# Relays.net
KiCad netlist of a schematic drawn in Altium Designer
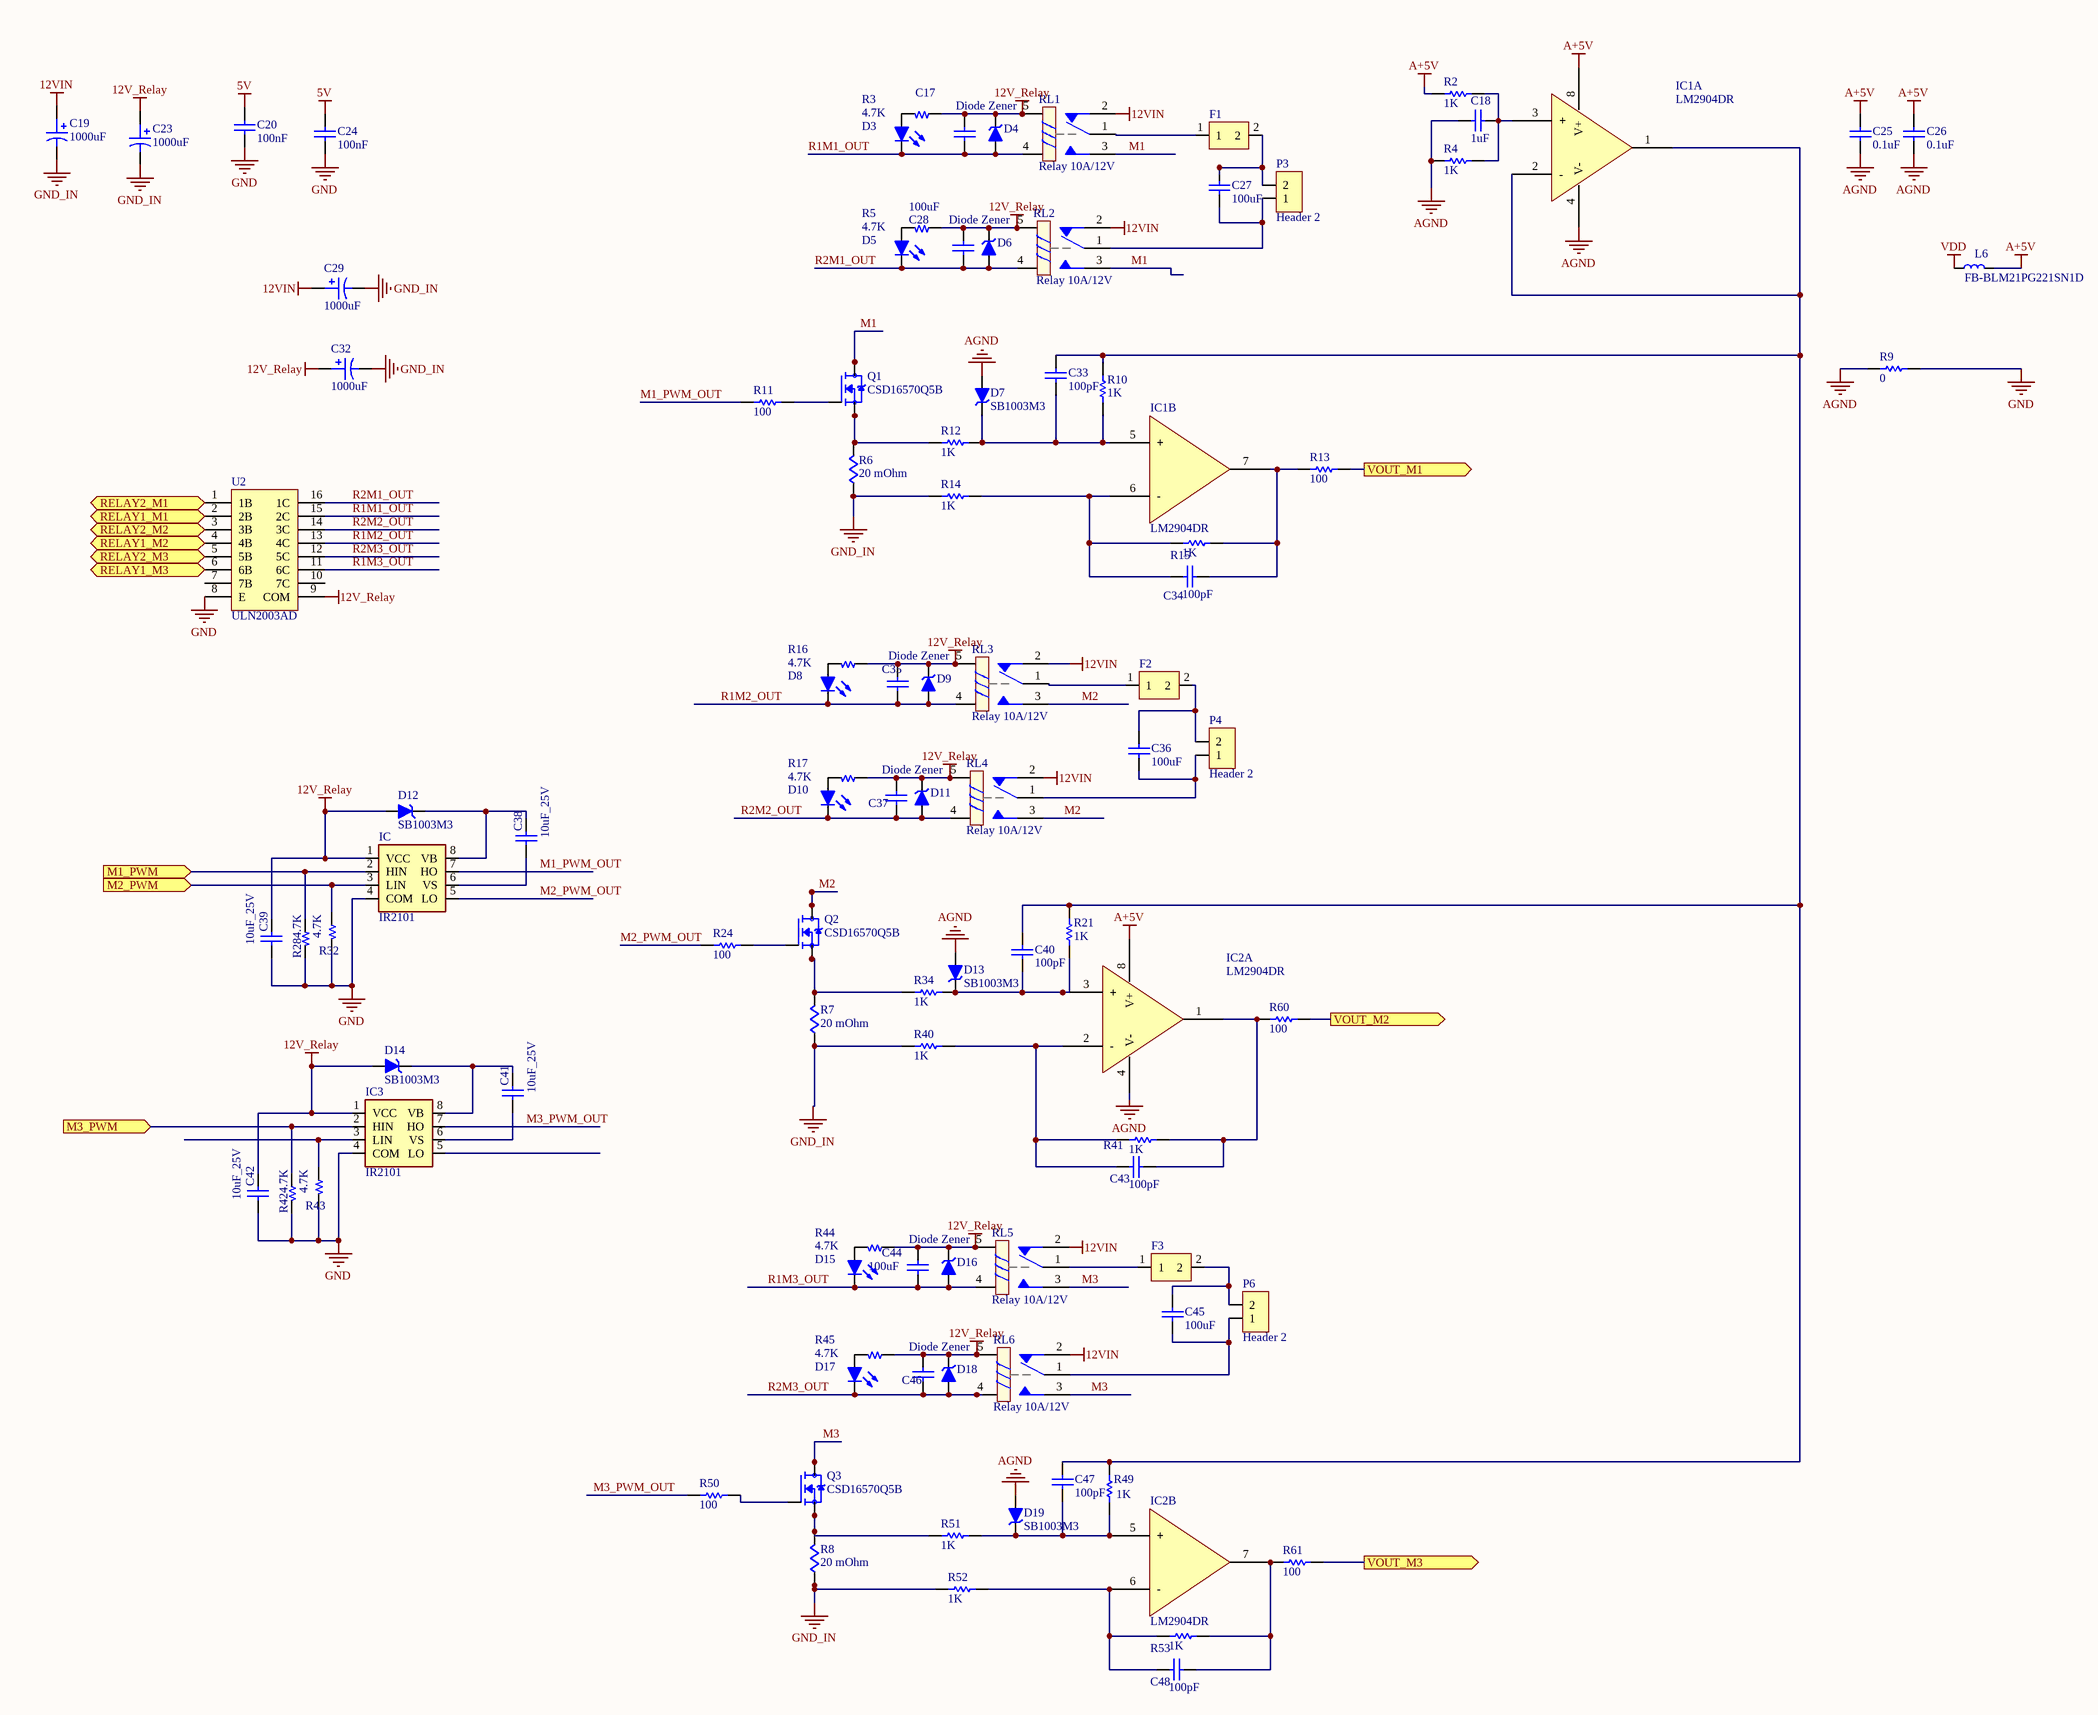
[diagram p0: Relays.SchDoc]

(export (version "E")
  (design (tool "Eeschema 10.0.6"))
  (components
    (comp (ref "C17")
      (value "Cap Non-pol")
      (footprint "C 0805")
      (description "Non-polarized Capacitor")
      (fields (field (name "PUBLISHER") "Altium Limited"))
      (libsource (lib "phong") (part "Cap Non-pol"))
    )
    (comp (ref "C18")
      (value "1uF")
      (footprint "C 0805")
      (description "Non-polarized Capacitor")
      (fields (field (name "Comment") "Cap Non-pol") (field (name "PUBLISHER") "Altium Limited"))
      (libsource (lib "phong") (part "Cap Non-pol"))
    )
    (comp (ref "C19")
      (value "1000uF")
      (footprint "CAP/D100/H200/LS50")
      (description "Polarized Capacitor")
      (fields (field (name "Comment") "Cap Pol") (field (name "PUBLISHER") "Altium Limited"))
      (libsource (lib "phong") (part "Cap Pol"))
    )
    (comp (ref "C20")
      (value "100nF")
      (footprint "C 0805")
      (description "Non-polarized Capacitor")
      (fields (field (name "Comment") "Cap Non-pol") (field (name "PUBLISHER") "Altium Limited"))
      (libsource (lib "phong") (part "Cap Non-pol"))
    )
    (comp (ref "C23")
      (value "1000uF")
      (footprint "CAP/D100/H200/LS50")
      (description "Polarized Capacitor")
      (fields (field (name "Comment") "Cap Pol") (field (name "PUBLISHER") "Altium Limited"))
      (libsource (lib "phong") (part "Cap Pol"))
    )
    (comp (ref "C24")
      (value "100nF")
      (footprint "C 0805")
      (description "Non-polarized Capacitor")
      (fields (field (name "Comment") "Cap Non-pol") (field (name "PUBLISHER") "Altium Limited"))
      (libsource (lib "phong") (part "Cap Non-pol"))
    )
    (comp (ref "C25")
      (value "0.1uF")
      (footprint "C 0805")
      (description "Non-polarized Capacitor")
      (fields (field (name "Comment") "Cap Non-pol") (field (name "PUBLISHER") "Altium Limited"))
      (libsource (lib "phong") (part "Cap Non-pol"))
    )
    (comp (ref "C26")
      (value "0.1uF")
      (footprint "C 0805")
      (description "Non-polarized Capacitor")
      (fields (field (name "Comment") "Cap Non-pol") (field (name "PUBLISHER") "Altium Limited"))
      (libsource (lib "phong") (part "Cap Non-pol"))
    )
    (comp (ref "C27")
      (value "100uF")
      (footprint "CAP Ceramic/W200")
      (description "Non-polarized Capacitor")
      (fields (field (name "Comment") "Cap Non-pol") (field (name "PUBLISHER") "Altium Limited"))
      (libsource (lib "phong") (part "Cap Non-pol"))
    )
    (comp (ref "C28")
      (value "100uF")
      (footprint "C 0805")
      (description "Non-polarized Capacitor")
      (fields (field (name "Comment") "Cap Non-pol") (field (name "PUBLISHER") "Altium Limited"))
      (libsource (lib "phong") (part "Cap Non-pol"))
    )
    (comp (ref "C29")
      (value "1000uF")
      (footprint "CAP/D100/H200/LS50")
      (description "Polarized Capacitor")
      (fields (field (name "Comment") "Cap Pol") (field (name "PUBLISHER") "Altium Limited"))
      (libsource (lib "phong") (part "Cap Pol"))
    )
    (comp (ref "C32")
      (value "1000uF")
      (footprint "CAP/D100/H200/LS50")
      (description "Polarized Capacitor")
      (fields (field (name "Comment") "Cap Pol") (field (name "PUBLISHER") "Altium Limited"))
      (libsource (lib "phong") (part "Cap Pol"))
    )
    (comp (ref "C33")
      (value "100pF")
      (footprint "C 0805")
      (description "Non-polarized Capacitor")
      (fields (field (name "Comment") "Cap Non-pol") (field (name "PUBLISHER") "Altium Limited"))
      (libsource (lib "phong") (part "Cap Non-pol"))
    )
    (comp (ref "C34")
      (value "100pF")
      (footprint "C 0805")
      (description "Non-polarized Capacitor")
      (fields (field (name "Comment") "Cap Non-pol") (field (name "PUBLISHER") "Altium Limited"))
      (libsource (lib "phong") (part "Cap Non-pol"))
    )
    (comp (ref "C35")
      (value "Cap Non-pol")
      (footprint "C 0805")
      (description "Non-polarized Capacitor")
      (fields (field (name "PUBLISHER") "Altium Limited"))
      (libsource (lib "phong") (part "Cap Non-pol"))
    )
    (comp (ref "C36")
      (value "100uF")
      (footprint "CAP Ceramic/W200")
      (description "Non-polarized Capacitor")
      (fields (field (name "Comment") "Cap Non-pol") (field (name "PUBLISHER") "Altium Limited"))
      (libsource (lib "phong") (part "Cap Non-pol"))
    )
    (comp (ref "C37")
      (value "Cap Non-pol")
      (footprint "C 0805")
      (description "Non-polarized Capacitor")
      (fields (field (name "PUBLISHER") "Altium Limited"))
      (libsource (lib "phong") (part "Cap Non-pol"))
    )
    (comp (ref "C38")
      (value "10uF_25V")
      (footprint "C 0805")
      (description "Non-polarized Capacitor")
      (fields (field (name "PUBLISHER") "Altium Limited"))
      (libsource (lib "phong") (part "Cap Non-pol"))
    )
    (comp (ref "C39")
      (value "10uF_25V")
      (footprint "C 0805")
      (description "Non-polarized Capacitor")
      (fields (field (name "PUBLISHER") "Altium Limited"))
      (libsource (lib "phong") (part "Cap Non-pol"))
    )
    (comp (ref "C40")
      (value "100pF")
      (footprint "C 0805")
      (description "Non-polarized Capacitor")
      (fields (field (name "Comment") "Cap Non-pol") (field (name "PUBLISHER") "Altium Limited"))
      (libsource (lib "phong") (part "Cap Non-pol"))
    )
    (comp (ref "C41")
      (value "10uF_25V")
      (footprint "C 0805")
      (description "Non-polarized Capacitor")
      (fields (field (name "PUBLISHER") "Altium Limited"))
      (libsource (lib "phong") (part "Cap Non-pol"))
    )
    (comp (ref "C42")
      (value "10uF_25V")
      (footprint "C 0805")
      (description "Non-polarized Capacitor")
      (fields (field (name "PUBLISHER") "Altium Limited"))
      (libsource (lib "phong") (part "Cap Non-pol"))
    )
    (comp (ref "C43")
      (value "100pF")
      (footprint "C 0805")
      (description "Non-polarized Capacitor")
      (fields (field (name "Comment") "Cap Non-pol") (field (name "PUBLISHER") "Altium Limited"))
      (libsource (lib "phong") (part "Cap Non-pol"))
    )
    (comp (ref "C44")
      (value "100uF")
      (footprint "C 0805")
      (description "Non-polarized Capacitor")
      (fields (field (name "Comment") "Cap Non-pol") (field (name "PUBLISHER") "Altium Limited"))
      (libsource (lib "phong") (part "Cap Non-pol"))
    )
    (comp (ref "C45")
      (value "100uF")
      (footprint "CAP Ceramic/W200")
      (description "Non-polarized Capacitor")
      (fields (field (name "Comment") "Cap Non-pol") (field (name "PUBLISHER") "Altium Limited"))
      (libsource (lib "phong") (part "Cap Non-pol"))
    )
    (comp (ref "C46")
      (value "Cap Non-pol")
      (footprint "C 0805")
      (description "Non-polarized Capacitor")
      (fields (field (name "PUBLISHER") "Altium Limited"))
      (libsource (lib "phong") (part "Cap Non-pol"))
    )
    (comp (ref "C47")
      (value "100pF")
      (footprint "C 0805")
      (description "Non-polarized Capacitor")
      (fields (field (name "Comment") "Cap Non-pol") (field (name "PUBLISHER") "Altium Limited"))
      (libsource (lib "phong") (part "Cap Non-pol"))
    )
    (comp (ref "C48")
      (value "100pF")
      (footprint "C 0805")
      (description "Non-polarized Capacitor")
      (fields (field (name "Comment") "Cap Non-pol") (field (name "PUBLISHER") "Altium Limited"))
      (libsource (lib "phong") (part "Cap Non-pol"))
    )
    (comp (ref "D3")
      (value "Led")
      (footprint "Led 0805 RED")
      (description "LED RED CLEAR 0805 SMD")
      (libsource (lib "chipfc_altium_libs") (part "Led"))
    )
    (comp (ref "D4")
      (value "Diode Zener")
      (footprint "SOD80C Wave")
      (description "Zener Diode")
      (fields (field (name "PUBLISHER") "Altium Limited"))
      (libsource (lib "BKIT4U_LIB") (part "Diode Zener"))
    )
    (comp (ref "D5")
      (value "Led")
      (footprint "Led 0805 RED")
      (description "LED RED CLEAR 0805 SMD")
      (libsource (lib "chipfc_altium_libs") (part "Led"))
    )
    (comp (ref "D6")
      (value "Diode Zener")
      (footprint "SOD80C Wave")
      (description "Zener Diode")
      (fields (field (name "PUBLISHER") "Altium Limited"))
      (libsource (lib "BKIT4U_LIB") (part "Diode Zener"))
    )
    (comp (ref "D7")
      (value "SB1003M3")
      (footprint "DO-214AC (SMA)")
      (description "Zener Diode")
      (libsource (lib "ChipFC_Lib") (part "Diode Zener"))
    )
    (comp (ref "D8")
      (value "Led")
      (footprint "Led 0805 RED")
      (description "LED RED CLEAR 0805 SMD")
      (libsource (lib "chipfc_altium_libs") (part "Led"))
    )
    (comp (ref "D9")
      (value "Diode Zener")
      (footprint "SOD80C Wave")
      (description "Zener Diode")
      (fields (field (name "PUBLISHER") "Altium Limited"))
      (libsource (lib "BKIT4U_LIB") (part "Diode Zener"))
    )
    (comp (ref "D10")
      (value "Led")
      (footprint "Led 0805 RED")
      (description "LED RED CLEAR 0805 SMD")
      (libsource (lib "chipfc_altium_libs") (part "Led"))
    )
    (comp (ref "D11")
      (value "Diode Zener")
      (footprint "SOD80C Wave")
      (description "Zener Diode")
      (fields (field (name "PUBLISHER") "Altium Limited"))
      (libsource (lib "BKIT4U_LIB") (part "Diode Zener"))
    )
    (comp (ref "D12")
      (value "SB1003M3")
      (footprint "DO-214AC (SMA)")
      (description "Zener Diode")
      (libsource (lib "ChipFC_Lib") (part "Diode Zener"))
    )
    (comp (ref "D13")
      (value "SB1003M3")
      (footprint "DO-214AC (SMA)")
      (description "Zener Diode")
      (libsource (lib "ChipFC_Lib") (part "Diode Zener"))
    )
    (comp (ref "D14")
      (value "SB1003M3")
      (footprint "DO-214AC (SMA)")
      (description "Zener Diode")
      (libsource (lib "ChipFC_Lib") (part "Diode Zener"))
    )
    (comp (ref "D15")
      (value "Led")
      (footprint "Led 0805 RED")
      (description "LED RED CLEAR 0805 SMD")
      (libsource (lib "chipfc_altium_libs") (part "Led"))
    )
    (comp (ref "D16")
      (value "Diode Zener")
      (footprint "SOD80C Wave")
      (description "Zener Diode")
      (fields (field (name "PUBLISHER") "Altium Limited"))
      (libsource (lib "BKIT4U_LIB") (part "Diode Zener"))
    )
    (comp (ref "D17")
      (value "Led")
      (footprint "Led 0805 RED")
      (description "LED RED CLEAR 0805 SMD")
      (libsource (lib "chipfc_altium_libs") (part "Led"))
    )
    (comp (ref "D18")
      (value "Diode Zener")
      (footprint "SOD80C Wave")
      (description "Zener Diode")
      (fields (field (name "PUBLISHER") "Altium Limited"))
      (libsource (lib "BKIT4U_LIB") (part "Diode Zener"))
    )
    (comp (ref "D19")
      (value "SB1003M3")
      (footprint "DO-214AC (SMA)")
      (description "Zener Diode")
      (libsource (lib "ChipFC_Lib") (part "Diode Zener"))
    )
    (comp (ref "F1")
      (value "FUSE_DCAR_HOLDER")
      (footprint "DCAR Fuse holder")
      (libsource (lib "FUSE_DCAR_HOLDER") (part "FUSE_DCAR_HOLDER"))
    )
    (comp (ref "F2")
      (value "FUSE_DCAR_HOLDER")
      (footprint "DCAR Fuse holder")
      (libsource (lib "FUSE_DCAR_HOLDER") (part "FUSE_DCAR_HOLDER"))
    )
    (comp (ref "F3")
      (value "FUSE_DCAR_HOLDER")
      (footprint "DCAR Fuse holder")
      (libsource (lib "FUSE_DCAR_HOLDER") (part "FUSE_DCAR_HOLDER"))
    )
    (comp (ref "IC")
      (value "IR2101")
      (footprint "SOIC-8-I/SN")
      (description "Half-Bridge Gate Driver IC Non-Inverting 8-SOIC")
      (fields (field (name "MF") "Infineon"))
      (libsource (lib "IR2101") (part "IR2101"))
    )
    (comp (ref "IC1")
      (value "LM2904DR")
      (footprint "SOIC-8-I/SN")
      (description "IC OPAMP GP 2 CIRCUIT 8SOIC")
      (fields (field (name "MANUFACTURER") "Texas Instruments"))
      (libsource (lib "Celestial Altium Library - altium_library") (part "TI LM2904DR"))
    )
    (comp (ref "IC2")
      (value "LM2904DR")
      (footprint "SOIC-8-I/SN")
      (description "IC OPAMP GP 2 CIRCUIT 8SOIC")
      (fields (field (name "MANUFACTURER") "Texas Instruments"))
      (libsource (lib "Celestial Altium Library - altium_library") (part "TI LM2904DR"))
    )
    (comp (ref "IC3")
      (value "IR2101")
      (footprint "SOIC-8-I/SN")
      (description "Half-Bridge Gate Driver IC Non-Inverting 8-SOIC")
      (fields (field (name "MF") "Infineon"))
      (libsource (lib "IR2101") (part "IR2101"))
    )
    (comp (ref "L6")
      (value "FB-BLM21PG221SN1D")
      (footprint "L 0805 (2012)")
      (description "Inductor")
      (libsource (lib "chipfc_altium_libs") (part "Inductor"))
    )
    (comp (ref "P3")
      (value "Header 2")
      (footprint "HDR Domino 2")
      (description "Header, 2-Pin")
      (fields (field (name "PUBLISHER") "Altium Limited"))
      (libsource (lib "BKIT4U_LIB") (part "Header 2"))
    )
    (comp (ref "P4")
      (value "Header 2")
      (footprint "HDR Domino 2")
      (description "Header, 2-Pin")
      (fields (field (name "PUBLISHER") "Altium Limited"))
      (libsource (lib "BKIT4U_LIB") (part "Header 2"))
    )
    (comp (ref "P6")
      (value "Header 2")
      (footprint "HDR Domino 2")
      (description "Header, 2-Pin")
      (fields (field (name "PUBLISHER") "Altium Limited"))
      (libsource (lib "BKIT4U_LIB") (part "Header 2"))
    )
    (comp (ref "Q1")
      (value "CSD16570Q5B")
      (footprint "TRANS_CSD19502Q5BT")
      (description "N-Channel 30V 35A _Ta_ 2.8W _Ta_, 53W _Tc_ Surface Mount 8-VSONP _3x3.15_")
      (fields (field (name "MP") "CSD17577Q3A") (field (name "MF") "Texas Instruments"))
      (libsource (lib "CSD17577Q3A") (part "CSD17577Q3A"))
    )
    (comp (ref "Q2")
      (value "CSD16570Q5B")
      (footprint "TRANS_CSD19502Q5BT")
      (description "N-Channel 30V 35A _Ta_ 2.8W _Ta_, 53W _Tc_ Surface Mount 8-VSONP _3x3.15_")
      (fields (field (name "MP") "CSD17577Q3A") (field (name "MF") "Texas Instruments"))
      (libsource (lib "CSD17577Q3A") (part "CSD17577Q3A"))
    )
    (comp (ref "Q3")
      (value "CSD16570Q5B")
      (footprint "TRANS_CSD19502Q5BT")
      (description "N-Channel 30V 35A _Ta_ 2.8W _Ta_, 53W _Tc_ Surface Mount 8-VSONP _3x3.15_")
      (fields (field (name "MP") "CSD17577Q3A") (field (name "MF") "Texas Instruments"))
      (libsource (lib "CSD17577Q3A") (part "CSD17577Q3A"))
    )
    (comp (ref "R2")
      (value "1K")
      (footprint "R 0805")
      (description "Resistor")
      (fields (field (name "PUBLISHER") "Altium Limited"))
      (libsource (lib "BKIT4U_LIB") (part "Resistor"))
    )
    (comp (ref "R3")
      (value "4.7K")
      (footprint "R 0805")
      (description "RES SMD 4.7K OHM 1% 1/10W 0805")
      (libsource (lib "chipfc_altium_libs") (part "Resistor"))
    )
    (comp (ref "R4")
      (value "1K")
      (footprint "R 0805")
      (description "Resistor")
      (fields (field (name "PUBLISHER") "Altium Limited"))
      (libsource (lib "BKIT4U_LIB") (part "Resistor"))
    )
    (comp (ref "R5")
      (value "4.7K")
      (footprint "R 0805")
      (description "RES SMD 4.7K OHM 1% 1/10W 0805")
      (libsource (lib "chipfc_altium_libs") (part "Resistor"))
    )
    (comp (ref "R6")
      (value "20 mOhm")
      (footprint "R2512")
      (fields (field (name "Comment") "Resistor2"))
      (libsource (lib "AltiumOpenLibs") (part "Resistor2"))
    )
    (comp (ref "R7")
      (value "20 mOhm")
      (footprint "R2512")
      (fields (field (name "Comment") "Resistor2"))
      (libsource (lib "AltiumOpenLibs") (part "Resistor2"))
    )
    (comp (ref "R8")
      (value "20 mOhm")
      (footprint "R2512")
      (fields (field (name "Comment") "Resistor2"))
      (libsource (lib "AltiumOpenLibs") (part "Resistor2"))
    )
    (comp (ref "R9")
      (value "0")
      (footprint "R 0805")
      (description "Resistor")
      (fields (field (name "PUBLISHER") "Altium Limited"))
      (libsource (lib "BKIT4U_LIB") (part "Resistor"))
    )
    (comp (ref "R10")
      (value "1K")
      (footprint "R 0805")
      (description "Resistor")
      (fields (field (name "PUBLISHER") "Altium Limited"))
      (libsource (lib "BKIT4U_LIB") (part "Resistor"))
    )
    (comp (ref "R11")
      (value "100")
      (footprint "R 0805")
      (description "Resistor")
      (fields (field (name "PUBLISHER") "Altium Limited"))
      (libsource (lib "BKIT4U_LIB") (part "Resistor"))
    )
    (comp (ref "R12")
      (value "1K")
      (footprint "R 0805")
      (description "Resistor")
      (fields (field (name "PUBLISHER") "Altium Limited"))
      (libsource (lib "BKIT4U_LIB") (part "Resistor"))
    )
    (comp (ref "R13")
      (value "100")
      (footprint "R 0805")
      (description "Resistor")
      (fields (field (name "PUBLISHER") "Altium Limited"))
      (libsource (lib "BKIT4U_LIB") (part "Resistor"))
    )
    (comp (ref "R14")
      (value "1K")
      (footprint "R 0805")
      (description "Resistor")
      (fields (field (name "PUBLISHER") "Altium Limited"))
      (libsource (lib "BKIT4U_LIB") (part "Resistor"))
    )
    (comp (ref "R15")
      (value "1K")
      (footprint "R 0805")
      (description "Resistor")
      (fields (field (name "PUBLISHER") "Altium Limited"))
      (libsource (lib "BKIT4U_LIB") (part "Resistor"))
    )
    (comp (ref "R16")
      (value "4.7K")
      (footprint "R 0805")
      (description "RES SMD 4.7K OHM 1% 1/10W 0805")
      (libsource (lib "chipfc_altium_libs") (part "Resistor"))
    )
    (comp (ref "R17")
      (value "4.7K")
      (footprint "R 0805")
      (description "RES SMD 4.7K OHM 1% 1/10W 0805")
      (libsource (lib "chipfc_altium_libs") (part "Resistor"))
    )
    (comp (ref "R21")
      (value "1K")
      (footprint "R 0805")
      (description "Resistor")
      (fields (field (name "PUBLISHER") "Altium Limited"))
      (libsource (lib "BKIT4U_LIB") (part "Resistor"))
    )
    (comp (ref "R24")
      (value "100")
      (footprint "R 0805")
      (description "Resistor")
      (fields (field (name "PUBLISHER") "Altium Limited"))
      (libsource (lib "BKIT4U_LIB") (part "Resistor"))
    )
    (comp (ref "R28")
      (value "4.7K")
      (footprint "R 0805")
      (description "RES SMD 4.7K OHM 1% 1/10W 0805")
      (libsource (lib "chipfc_altium_libs") (part "Resistor"))
    )
    (comp (ref "R32")
      (value "4.7K")
      (footprint "R 0805")
      (description "RES SMD 4.7K OHM 1% 1/10W 0805")
      (libsource (lib "chipfc_altium_libs") (part "Resistor"))
    )
    (comp (ref "R34")
      (value "1K")
      (footprint "R 0805")
      (description "Resistor")
      (fields (field (name "PUBLISHER") "Altium Limited"))
      (libsource (lib "BKIT4U_LIB") (part "Resistor"))
    )
    (comp (ref "R40")
      (value "1K")
      (footprint "R 0805")
      (description "Resistor")
      (fields (field (name "PUBLISHER") "Altium Limited"))
      (libsource (lib "BKIT4U_LIB") (part "Resistor"))
    )
    (comp (ref "R41")
      (value "1K")
      (footprint "R 0805")
      (description "Resistor")
      (fields (field (name "PUBLISHER") "Altium Limited"))
      (libsource (lib "BKIT4U_LIB") (part "Resistor"))
    )
    (comp (ref "R42")
      (value "4.7K")
      (footprint "R 0805")
      (description "RES SMD 4.7K OHM 1% 1/10W 0805")
      (libsource (lib "chipfc_altium_libs") (part "Resistor"))
    )
    (comp (ref "R43")
      (value "4.7K")
      (footprint "R 0805")
      (description "RES SMD 4.7K OHM 1% 1/10W 0805")
      (libsource (lib "chipfc_altium_libs") (part "Resistor"))
    )
    (comp (ref "R44")
      (value "4.7K")
      (footprint "R 0805")
      (description "RES SMD 4.7K OHM 1% 1/10W 0805")
      (libsource (lib "chipfc_altium_libs") (part "Resistor"))
    )
    (comp (ref "R45")
      (value "4.7K")
      (footprint "R 0805")
      (description "RES SMD 4.7K OHM 1% 1/10W 0805")
      (libsource (lib "chipfc_altium_libs") (part "Resistor"))
    )
    (comp (ref "R49")
      (value "1K")
      (footprint "R 0805")
      (description "Resistor")
      (fields (field (name "PUBLISHER") "Altium Limited"))
      (libsource (lib "BKIT4U_LIB") (part "Resistor"))
    )
    (comp (ref "R50")
      (value "100")
      (footprint "R 0805")
      (description "Resistor")
      (fields (field (name "PUBLISHER") "Altium Limited"))
      (libsource (lib "BKIT4U_LIB") (part "Resistor"))
    )
    (comp (ref "R51")
      (value "1K")
      (footprint "R 0805")
      (description "Resistor")
      (fields (field (name "PUBLISHER") "Altium Limited"))
      (libsource (lib "BKIT4U_LIB") (part "Resistor"))
    )
    (comp (ref "R52")
      (value "1K")
      (footprint "R 0805")
      (description "Resistor")
      (fields (field (name "PUBLISHER") "Altium Limited"))
      (libsource (lib "BKIT4U_LIB") (part "Resistor"))
    )
    (comp (ref "R53")
      (value "1K")
      (footprint "R 0805")
      (description "Resistor")
      (fields (field (name "PUBLISHER") "Altium Limited"))
      (libsource (lib "BKIT4U_LIB") (part "Resistor"))
    )
    (comp (ref "R60")
      (value "100")
      (footprint "R 0805")
      (description "Resistor")
      (fields (field (name "PUBLISHER") "Altium Limited"))
      (libsource (lib "BKIT4U_LIB") (part "Resistor"))
    )
    (comp (ref "R61")
      (value "100")
      (footprint "R 0805")
      (description "Resistor")
      (fields (field (name "PUBLISHER") "Altium Limited"))
      (libsource (lib "BKIT4U_LIB") (part "Resistor"))
    )
    (comp (ref "RL1")
      (value "Relay 10A/12V")
      (footprint "RL_SPDT_20A_SMALL")
      (description "Relay SPDT,10A - 12VDC 5 Pin")
      (libsource (lib "BKIT4U_LIB") (part "Relay 1"))
    )
    (comp (ref "RL2")
      (value "Relay 10A/12V")
      (footprint "RL_SPDT_20A_SMALL")
      (description "Relay SPDT,10A - 12VDC 5 Pin")
      (libsource (lib "BKIT4U_LIB") (part "Relay 1"))
    )
    (comp (ref "RL3")
      (value "Relay 10A/12V")
      (footprint "RL_SPDT_20A_SMALL")
      (description "Relay SPDT,10A - 12VDC 5 Pin")
      (libsource (lib "BKIT4U_LIB") (part "Relay 1"))
    )
    (comp (ref "RL4")
      (value "Relay 10A/12V")
      (footprint "RL_SPDT_20A_SMALL")
      (description "Relay SPDT,10A - 12VDC 5 Pin")
      (libsource (lib "BKIT4U_LIB") (part "Relay 1"))
    )
    (comp (ref "RL5")
      (value "Relay 10A/12V")
      (footprint "RL_SPDT_20A_SMALL")
      (description "Relay SPDT,10A - 12VDC 5 Pin")
      (libsource (lib "BKIT4U_LIB") (part "Relay 1"))
    )
    (comp (ref "RL6")
      (value "Relay 10A/12V")
      (footprint "RL_SPDT_20A_SMALL")
      (description "Relay SPDT,10A - 12VDC 5 Pin")
      (libsource (lib "BKIT4U_LIB") (part "Relay 1"))
    )
    (comp (ref "U2")
      (value "ULN2003AD")
      (footprint "SOIC-16")
      (description "IC PWR RELAY 7NPN 1:1 16SOIC")
      (libsource (lib "chipfc_altium_libs") (part "ULN2003"))
    )
  )
  (nets
    (net (code "1") (name "/M1") (class "Default")
      (node (ref "Q1") (pin "9") (pinfunction "D_9") (pintype "passive"))
      (node (ref "Q1") (pin "9_1") (pinfunction "D_9_1") (pintype "passive"))
      (node (ref "Q1") (pin "9_2") (pinfunction "D_9_2") (pintype "passive"))
      (node (ref "Q1") (pin "9_3") (pinfunction "D_9_3") (pintype "passive"))
      (node (ref "Q1") (pin "9_4") (pinfunction "D_9_4") (pintype "passive"))
      (node (ref "Q1") (pin "9_5") (pinfunction "D_9_5") (pintype "passive"))
      (node (ref "Q1") (pin "9_6") (pinfunction "D_9_6") (pintype "passive"))
      (node (ref "Q1") (pin "9_7") (pinfunction "D_9_7") (pintype "passive"))
      (node (ref "RL1") (pin "3") (pinfunction "3_3") (pintype "passive"))
      (node (ref "RL2") (pin "3") (pinfunction "3_3") (pintype "passive"))
    )
    (net (code "2") (name "/M1_PWM") (class "Default")
      (node (ref "IC") (pin "2") (pinfunction "HIN_2") (pintype "bidirectional"))
      (node (ref "R28") (pin "1") (pinfunction "1_1") (pintype "passive"))
    )
    (net (code "3") (name "/M1_PWM_OUT") (class "Default")
      (node (ref "IC") (pin "7") (pinfunction "HO_7") (pintype "bidirectional"))
      (node (ref "R11") (pin "2") (pinfunction "2_2") (pintype "passive"))
    )
    (net (code "4") (name "/M2") (class "Default")
      (node (ref "Q2") (pin "9") (pinfunction "D_9") (pintype "passive"))
      (node (ref "Q2") (pin "9_1") (pinfunction "D_9_1") (pintype "passive"))
      (node (ref "Q2") (pin "9_2") (pinfunction "D_9_2") (pintype "passive"))
      (node (ref "Q2") (pin "9_3") (pinfunction "D_9_3") (pintype "passive"))
      (node (ref "Q2") (pin "9_4") (pinfunction "D_9_4") (pintype "passive"))
      (node (ref "Q2") (pin "9_5") (pinfunction "D_9_5") (pintype "passive"))
      (node (ref "Q2") (pin "9_6") (pinfunction "D_9_6") (pintype "passive"))
      (node (ref "Q2") (pin "9_7") (pinfunction "D_9_7") (pintype "passive"))
      (node (ref "RL3") (pin "3") (pinfunction "3_3") (pintype "passive"))
      (node (ref "RL4") (pin "3") (pinfunction "3_3") (pintype "passive"))
    )
    (net (code "5") (name "/M2_PWM") (class "Default")
      (node (ref "IC") (pin "3") (pinfunction "LIN_3") (pintype "bidirectional"))
      (node (ref "R32") (pin "1") (pinfunction "1_1") (pintype "passive"))
    )
    (net (code "6") (name "/M2_PWM_OUT") (class "Default")
      (node (ref "IC") (pin "5") (pinfunction "LO_5") (pintype "bidirectional"))
      (node (ref "R24") (pin "2") (pinfunction "2_2") (pintype "passive"))
    )
    (net (code "7") (name "/M3") (class "Default")
      (node (ref "Q3") (pin "9") (pinfunction "D_9") (pintype "passive"))
      (node (ref "Q3") (pin "9_1") (pinfunction "D_9_1") (pintype "passive"))
      (node (ref "Q3") (pin "9_2") (pinfunction "D_9_2") (pintype "passive"))
      (node (ref "Q3") (pin "9_3") (pinfunction "D_9_3") (pintype "passive"))
      (node (ref "Q3") (pin "9_4") (pinfunction "D_9_4") (pintype "passive"))
      (node (ref "Q3") (pin "9_5") (pinfunction "D_9_5") (pintype "passive"))
      (node (ref "Q3") (pin "9_6") (pinfunction "D_9_6") (pintype "passive"))
      (node (ref "Q3") (pin "9_7") (pinfunction "D_9_7") (pintype "passive"))
      (node (ref "RL5") (pin "3") (pinfunction "3_3") (pintype "passive"))
      (node (ref "RL6") (pin "3") (pinfunction "3_3") (pintype "passive"))
    )
    (net (code "8") (name "/M3_PWM") (class "Default")
      (node (ref "IC3") (pin "2") (pinfunction "HIN_2") (pintype "bidirectional"))
      (node (ref "R42") (pin "1") (pinfunction "1_1") (pintype "passive"))
    )
    (net (code "9") (name "/M3_PWM_OUT") (class "Default")
      (node (ref "IC3") (pin "7") (pinfunction "HO_7") (pintype "bidirectional"))
      (node (ref "R50") (pin "2") (pinfunction "2_2") (pintype "passive"))
    )
    (net (code "10") (name "/R1M1_OUT") (class "Default")
      (node (ref "C17") (pin "1") (pinfunction "1_1") (pintype "passive"))
      (node (ref "D3") (pin "2") (pinfunction "K_2") (pintype "passive"))
      (node (ref "D4") (pin "1") (pinfunction "A_1") (pintype "passive"))
      (node (ref "RL1") (pin "4") (pinfunction "4_4") (pintype "passive"))
      (node (ref "U2") (pin "15") (pinfunction "2C_15") (pintype "passive"))
    )
    (net (code "11") (name "/R1M2_OUT") (class "Default")
      (node (ref "C35") (pin "1") (pinfunction "1_1") (pintype "passive"))
      (node (ref "D8") (pin "2") (pinfunction "K_2") (pintype "passive"))
      (node (ref "D9") (pin "1") (pinfunction "A_1") (pintype "passive"))
      (node (ref "RL3") (pin "4") (pinfunction "4_4") (pintype "passive"))
      (node (ref "U2") (pin "13") (pinfunction "4C_13") (pintype "passive"))
    )
    (net (code "12") (name "/R1M3_OUT") (class "Default")
      (node (ref "C44") (pin "1") (pinfunction "1_1") (pintype "passive"))
      (node (ref "D15") (pin "2") (pinfunction "K_2") (pintype "passive"))
      (node (ref "D16") (pin "1") (pinfunction "A_1") (pintype "passive"))
      (node (ref "RL5") (pin "4") (pinfunction "4_4") (pintype "passive"))
      (node (ref "U2") (pin "11") (pinfunction "6C_11") (pintype "passive"))
    )
    (net (code "13") (name "/R2M1_OUT") (class "Default")
      (node (ref "C28") (pin "1") (pinfunction "1_1") (pintype "passive"))
      (node (ref "D5") (pin "2") (pinfunction "K_2") (pintype "passive"))
      (node (ref "D6") (pin "1") (pinfunction "A_1") (pintype "passive"))
      (node (ref "RL2") (pin "4") (pinfunction "4_4") (pintype "passive"))
      (node (ref "U2") (pin "16") (pinfunction "1C_16") (pintype "passive"))
    )
    (net (code "14") (name "/R2M2_OUT") (class "Default")
      (node (ref "C37") (pin "1") (pinfunction "1_1") (pintype "passive"))
      (node (ref "D10") (pin "2") (pinfunction "K_2") (pintype "passive"))
      (node (ref "D11") (pin "1") (pinfunction "A_1") (pintype "passive"))
      (node (ref "RL4") (pin "4") (pinfunction "4_4") (pintype "passive"))
      (node (ref "U2") (pin "14") (pinfunction "3C_14") (pintype "passive"))
    )
    (net (code "15") (name "/R2M3_OUT") (class "Default")
      (node (ref "C46") (pin "1") (pinfunction "1_1") (pintype "passive"))
      (node (ref "D17") (pin "2") (pinfunction "K_2") (pintype "passive"))
      (node (ref "D18") (pin "1") (pinfunction "A_1") (pintype "passive"))
      (node (ref "RL6") (pin "4") (pinfunction "4_4") (pintype "passive"))
      (node (ref "U2") (pin "12") (pinfunction "5C_12") (pintype "passive"))
    )
    (net (code "16") (name "/RELAY1_M1") (class "Default")
      (node (ref "U2") (pin "2") (pinfunction "2B_2") (pintype "passive"))
    )
    (net (code "17") (name "/RELAY1_M2") (class "Default")
      (node (ref "U2") (pin "4") (pinfunction "4B_4") (pintype "passive"))
    )
    (net (code "18") (name "/RELAY1_M3") (class "Default")
      (node (ref "U2") (pin "6") (pinfunction "6B_6") (pintype "passive"))
    )
    (net (code "19") (name "/RELAY2_M1") (class "Default")
      (node (ref "U2") (pin "1") (pinfunction "1B_1") (pintype "passive"))
    )
    (net (code "20") (name "/RELAY2_M2") (class "Default")
      (node (ref "U2") (pin "3") (pinfunction "3B_3") (pintype "passive"))
    )
    (net (code "21") (name "/RELAY2_M3") (class "Default")
      (node (ref "U2") (pin "5") (pinfunction "5B_5") (pintype "passive"))
    )
    (net (code "22") (name "/VOUT_M1") (class "Default")
      (node (ref "R13") (pin "1") (pinfunction "1_1") (pintype "passive"))
    )
    (net (code "23") (name "/VOUT_M2") (class "Default")
      (node (ref "R60") (pin "1") (pinfunction "1_1") (pintype "passive"))
    )
    (net (code "24") (name "/VOUT_M3") (class "Default")
      (node (ref "R61") (pin "1") (pinfunction "1_1") (pintype "passive"))
    )
    (net (code "25") (name "5V") (class "Default")
      (node (ref "C20") (pin "2") (pinfunction "2_2") (pintype "passive"))
      (node (ref "C24") (pin "2") (pinfunction "2_2") (pintype "passive"))
    )
    (net (code "26") (name "12VIN") (class "Default")
      (node (ref "C19") (pin "1") (pinfunction "1_1") (pintype "passive"))
      (node (ref "C29") (pin "1") (pinfunction "1_1") (pintype "passive"))
      (node (ref "RL1") (pin "2") (pinfunction "2_2") (pintype "passive"))
      (node (ref "RL2") (pin "2") (pinfunction "2_2") (pintype "passive"))
      (node (ref "RL3") (pin "2") (pinfunction "2_2") (pintype "passive"))
      (node (ref "RL4") (pin "2") (pinfunction "2_2") (pintype "passive"))
      (node (ref "RL5") (pin "2") (pinfunction "2_2") (pintype "passive"))
      (node (ref "RL6") (pin "2") (pinfunction "2_2") (pintype "passive"))
    )
    (net (code "27") (name "12V_Relay") (class "Default")
      (node (ref "C17") (pin "2") (pinfunction "2_2") (pintype "passive"))
      (node (ref "C23") (pin "1") (pinfunction "1_1") (pintype "passive"))
      (node (ref "C28") (pin "2") (pinfunction "2_2") (pintype "passive"))
      (node (ref "C32") (pin "1") (pinfunction "1_1") (pintype "passive"))
      (node (ref "C35") (pin "2") (pinfunction "2_2") (pintype "passive"))
      (node (ref "C37") (pin "2") (pinfunction "2_2") (pintype "passive"))
      (node (ref "C39") (pin "2") (pinfunction "2_2") (pintype "passive"))
      (node (ref "C42") (pin "2") (pinfunction "2_2") (pintype "passive"))
      (node (ref "C44") (pin "2") (pinfunction "2_2") (pintype "passive"))
      (node (ref "C46") (pin "2") (pinfunction "2_2") (pintype "passive"))
      (node (ref "D11") (pin "2") (pinfunction "K_2") (pintype "passive"))
      (node (ref "D12") (pin "1") (pinfunction "A_1") (pintype "passive"))
      (node (ref "D14") (pin "1") (pinfunction "A_1") (pintype "passive"))
      (node (ref "D16") (pin "2") (pinfunction "K_2") (pintype "passive"))
      (node (ref "D18") (pin "2") (pinfunction "K_2") (pintype "passive"))
      (node (ref "D4") (pin "2") (pinfunction "K_2") (pintype "passive"))
      (node (ref "D6") (pin "2") (pinfunction "K_2") (pintype "passive"))
      (node (ref "D9") (pin "2") (pinfunction "K_2") (pintype "passive"))
      (node (ref "IC") (pin "1") (pinfunction "VCC_1") (pintype "bidirectional"))
      (node (ref "IC3") (pin "1") (pinfunction "VCC_1") (pintype "bidirectional"))
      (node (ref "R16") (pin "1") (pinfunction "1_1") (pintype "passive"))
      (node (ref "R17") (pin "1") (pinfunction "1_1") (pintype "passive"))
      (node (ref "R3") (pin "1") (pinfunction "1_1") (pintype "passive"))
      (node (ref "R44") (pin "1") (pinfunction "1_1") (pintype "passive"))
      (node (ref "R45") (pin "1") (pinfunction "1_1") (pintype "passive"))
      (node (ref "R5") (pin "1") (pinfunction "1_1") (pintype "passive"))
      (node (ref "RL1") (pin "5") (pinfunction "5_5") (pintype "passive"))
      (node (ref "RL2") (pin "5") (pinfunction "5_5") (pintype "passive"))
      (node (ref "RL3") (pin "5") (pinfunction "5_5") (pintype "passive"))
      (node (ref "RL4") (pin "5") (pinfunction "5_5") (pintype "passive"))
      (node (ref "RL5") (pin "5") (pinfunction "5_5") (pintype "passive"))
      (node (ref "RL6") (pin "5") (pinfunction "5_5") (pintype "passive"))
      (node (ref "U2") (pin "9") (pinfunction "COM_9") (pintype "passive"))
    )
    (net (code "28") (name "A+5V") (class "Default")
      (node (ref "C25") (pin "2") (pinfunction "2_2") (pintype "passive"))
      (node (ref "C26") (pin "2") (pinfunction "2_2") (pintype "passive"))
      (node (ref "IC1") (pin "8") (pinfunction "V+_8") (pintype "passive"))
      (node (ref "IC2") (pin "8") (pinfunction "V+_8") (pintype "passive"))
      (node (ref "L6") (pin "2") (pinfunction "2_2") (pintype "passive"))
      (node (ref "R2") (pin "1") (pinfunction "1_1") (pintype "passive"))
    )
    (net (code "29") (name "AGND") (class "Default")
      (node (ref "C18") (pin "2") (pinfunction "2_2") (pintype "passive"))
      (node (ref "C25") (pin "1") (pinfunction "1_1") (pintype "passive"))
      (node (ref "C26") (pin "1") (pinfunction "1_1") (pintype "passive"))
      (node (ref "D13") (pin "1") (pinfunction "A_1") (pintype "passive"))
      (node (ref "D19") (pin "1") (pinfunction "A_1") (pintype "passive"))
      (node (ref "D7") (pin "1") (pinfunction "A_1") (pintype "passive"))
      (node (ref "IC1") (pin "4") (pinfunction "V-_4") (pintype "passive"))
      (node (ref "IC2") (pin "4") (pinfunction "V-_4") (pintype "passive"))
      (node (ref "R4") (pin "1") (pinfunction "1_1") (pintype "passive"))
      (node (ref "R9") (pin "1") (pinfunction "1_1") (pintype "passive"))
    )
    (net (code "30") (name "GND") (class "Default")
      (node (ref "C20") (pin "1") (pinfunction "1_1") (pintype "passive"))
      (node (ref "C24") (pin "1") (pinfunction "1_1") (pintype "passive"))
      (node (ref "C39") (pin "1") (pinfunction "1_1") (pintype "passive"))
      (node (ref "C42") (pin "1") (pinfunction "1_1") (pintype "passive"))
      (node (ref "IC") (pin "4") (pinfunction "COM_4") (pintype "bidirectional"))
      (node (ref "IC3") (pin "4") (pinfunction "COM_4") (pintype "bidirectional"))
      (node (ref "R28") (pin "2") (pinfunction "2_2") (pintype "passive"))
      (node (ref "R32") (pin "2") (pinfunction "2_2") (pintype "passive"))
      (node (ref "R42") (pin "2") (pinfunction "2_2") (pintype "passive"))
      (node (ref "R43") (pin "2") (pinfunction "2_2") (pintype "passive"))
      (node (ref "R9") (pin "2") (pinfunction "2_2") (pintype "passive"))
      (node (ref "U2") (pin "8") (pinfunction "E_8") (pintype "passive"))
    )
    (net (code "31") (name "GND_IN") (class "Default")
      (node (ref "C19") (pin "2") (pinfunction "2_2") (pintype "passive"))
      (node (ref "C23") (pin "2") (pinfunction "2_2") (pintype "passive"))
      (node (ref "C29") (pin "2") (pinfunction "2_2") (pintype "passive"))
      (node (ref "C32") (pin "2") (pinfunction "2_2") (pintype "passive"))
      (node (ref "R14") (pin "2") (pinfunction "2_2") (pintype "passive"))
      (node (ref "R40") (pin "2") (pinfunction "2_2") (pintype "passive"))
      (node (ref "R52") (pin "2") (pinfunction "2_2") (pintype "passive"))
      (node (ref "R6") (pin "1") (pinfunction "1_1") (pintype "passive"))
      (node (ref "R7") (pin "1") (pinfunction "1_1") (pintype "passive"))
      (node (ref "R8") (pin "1") (pinfunction "1_1") (pintype "passive"))
    )
    (net (code "32") (name "Net-(C27-Pad1)") (class "Default")
      (node (ref "C27") (pin "1") (pinfunction "1_1") (pintype "passive"))
      (node (ref "P3") (pin "1") (pinfunction "1_1") (pintype "passive"))
      (node (ref "RL2") (pin "1") (pinfunction "1_1") (pintype "passive"))
    )
    (net (code "33") (name "Net-(C27-Pad2)") (class "Default")
      (node (ref "C27") (pin "2") (pinfunction "2_2") (pintype "passive"))
      (node (ref "F1") (pin "2") (pinfunction "2_2") (pintype "passive"))
      (node (ref "P3") (pin "2") (pinfunction "2_2") (pintype "passive"))
    )
    (net (code "34") (name "Net-(C36-Pad1)") (class "Default")
      (node (ref "C36") (pin "1") (pinfunction "1_1") (pintype "passive"))
      (node (ref "P4") (pin "1") (pinfunction "1_1") (pintype "passive"))
      (node (ref "RL4") (pin "1") (pinfunction "1_1") (pintype "passive"))
    )
    (net (code "35") (name "Net-(C36-Pad2)") (class "Default")
      (node (ref "C36") (pin "2") (pinfunction "2_2") (pintype "passive"))
      (node (ref "F2") (pin "2") (pinfunction "2_2") (pintype "passive"))
      (node (ref "P4") (pin "2") (pinfunction "2_2") (pintype "passive"))
    )
    (net (code "36") (name "Net-(C45-Pad1)") (class "Default")
      (node (ref "C45") (pin "1") (pinfunction "1_1") (pintype "passive"))
      (node (ref "P6") (pin "1") (pinfunction "1_1") (pintype "passive"))
      (node (ref "RL6") (pin "1") (pinfunction "1_1") (pintype "passive"))
    )
    (net (code "37") (name "Net-(C45-Pad2)") (class "Default")
      (node (ref "C45") (pin "2") (pinfunction "2_2") (pintype "passive"))
      (node (ref "F3") (pin "2") (pinfunction "2_2") (pintype "passive"))
      (node (ref "P6") (pin "2") (pinfunction "2_2") (pintype "passive"))
    )
    (net (code "38") (name "Net-(D3-A)") (class "Default")
      (node (ref "D3") (pin "1") (pinfunction "A_1") (pintype "passive"))
      (node (ref "R3") (pin "2") (pinfunction "2_2") (pintype "passive"))
    )
    (net (code "39") (name "Net-(D5-A)") (class "Default")
      (node (ref "D5") (pin "1") (pinfunction "A_1") (pintype "passive"))
      (node (ref "R5") (pin "2") (pinfunction "2_2") (pintype "passive"))
    )
    (net (code "40") (name "Net-(D7-K)") (class "Default")
      (node (ref "C33") (pin "2") (pinfunction "2_2") (pintype "passive"))
      (node (ref "D7") (pin "2") (pinfunction "K_2") (pintype "passive"))
      (node (ref "IC1") (pin "5") (pinfunction "+_5") (pintype "passive"))
      (node (ref "R10") (pin "2") (pinfunction "2_2") (pintype "passive"))
      (node (ref "R12") (pin "1") (pinfunction "1_1") (pintype "passive"))
    )
    (net (code "41") (name "Net-(D8-A)") (class "Default")
      (node (ref "D8") (pin "1") (pinfunction "A_1") (pintype "passive"))
      (node (ref "R16") (pin "2") (pinfunction "2_2") (pintype "passive"))
    )
    (net (code "42") (name "Net-(D10-A)") (class "Default")
      (node (ref "D10") (pin "1") (pinfunction "A_1") (pintype "passive"))
      (node (ref "R17") (pin "2") (pinfunction "2_2") (pintype "passive"))
    )
    (net (code "43") (name "Net-(D12-K)") (class "Default")
      (node (ref "C38") (pin "2") (pinfunction "2_2") (pintype "passive"))
      (node (ref "D12") (pin "2") (pinfunction "K_2") (pintype "passive"))
      (node (ref "IC") (pin "8") (pinfunction "VB_8") (pintype "bidirectional"))
    )
    (net (code "44") (name "Net-(D13-K)") (class "Default")
      (node (ref "C40") (pin "2") (pinfunction "2_2") (pintype "passive"))
      (node (ref "D13") (pin "2") (pinfunction "K_2") (pintype "passive"))
      (node (ref "IC2") (pin "3") (pinfunction "+_3") (pintype "passive"))
      (node (ref "R21") (pin "2") (pinfunction "2_2") (pintype "passive"))
      (node (ref "R34") (pin "1") (pinfunction "1_1") (pintype "passive"))
    )
    (net (code "45") (name "Net-(D14-K)") (class "Default")
      (node (ref "C41") (pin "2") (pinfunction "2_2") (pintype "passive"))
      (node (ref "D14") (pin "2") (pinfunction "K_2") (pintype "passive"))
      (node (ref "IC3") (pin "8") (pinfunction "VB_8") (pintype "bidirectional"))
    )
    (net (code "46") (name "Net-(D15-A)") (class "Default")
      (node (ref "D15") (pin "1") (pinfunction "A_1") (pintype "passive"))
      (node (ref "R44") (pin "2") (pinfunction "2_2") (pintype "passive"))
    )
    (net (code "47") (name "Net-(D17-A)") (class "Default")
      (node (ref "D17") (pin "1") (pinfunction "A_1") (pintype "passive"))
      (node (ref "R45") (pin "2") (pinfunction "2_2") (pintype "passive"))
    )
    (net (code "48") (name "Net-(D19-K)") (class "Default")
      (node (ref "C47") (pin "2") (pinfunction "2_2") (pintype "passive"))
      (node (ref "D19") (pin "2") (pinfunction "K_2") (pintype "passive"))
      (node (ref "IC2") (pin "5") (pinfunction "+_5") (pintype "passive"))
      (node (ref "R49") (pin "2") (pinfunction "2_2") (pintype "passive"))
      (node (ref "R51") (pin "1") (pinfunction "1_1") (pintype "passive"))
    )
    (net (code "49") (name "Net-(F1-Pad1)") (class "Default")
      (node (ref "F1") (pin "1") (pinfunction "1_1") (pintype "passive"))
      (node (ref "RL1") (pin "1") (pinfunction "1_1") (pintype "passive"))
    )
    (net (code "50") (name "Net-(F2-Pad1)") (class "Default")
      (node (ref "F2") (pin "1") (pinfunction "1_1") (pintype "passive"))
      (node (ref "RL3") (pin "1") (pinfunction "1_1") (pintype "passive"))
    )
    (net (code "51") (name "Net-(F3-Pad1)") (class "Default")
      (node (ref "F3") (pin "1") (pinfunction "1_1") (pintype "passive"))
      (node (ref "RL5") (pin "1") (pinfunction "1_1") (pintype "passive"))
    )
    (net (code "52") (name "Net-(IC-VS)") (class "Default")
      (node (ref "C38") (pin "1") (pinfunction "1_1") (pintype "passive"))
      (node (ref "IC") (pin "6") (pinfunction "VS_6") (pintype "bidirectional"))
    )
    (net (code "53") (name "Net-(IC1A-+)") (class "Default")
      (node (ref "C18") (pin "1") (pinfunction "1_1") (pintype "passive"))
      (node (ref "IC1") (pin "3") (pinfunction "+_3") (pintype "passive"))
      (node (ref "R2") (pin "2") (pinfunction "2_2") (pintype "passive"))
      (node (ref "R4") (pin "2") (pinfunction "2_2") (pintype "passive"))
    )
    (net (code "54") (name "Net-(IC1A--)") (class "Default")
      (node (ref "C33") (pin "1") (pinfunction "1_1") (pintype "passive"))
      (node (ref "C40") (pin "1") (pinfunction "1_1") (pintype "passive"))
      (node (ref "C47") (pin "1") (pinfunction "1_1") (pintype "passive"))
      (node (ref "IC1") (pin "1") (pinfunction "OUTA_1") (pintype "passive"))
      (node (ref "IC1") (pin "2") (pinfunction "-_2") (pintype "passive"))
      (node (ref "R10") (pin "1") (pinfunction "1_1") (pintype "passive"))
      (node (ref "R21") (pin "1") (pinfunction "1_1") (pintype "passive"))
      (node (ref "R49") (pin "1") (pinfunction "1_1") (pintype "passive"))
    )
    (net (code "55") (name "Net-(IC1B--)") (class "Default")
      (node (ref "C34") (pin "2") (pinfunction "2_2") (pintype "passive"))
      (node (ref "IC1") (pin "6") (pinfunction "-_6") (pintype "passive"))
      (node (ref "R14") (pin "1") (pinfunction "1_1") (pintype "passive"))
      (node (ref "R15") (pin "2") (pinfunction "2_2") (pintype "passive"))
    )
    (net (code "56") (name "Net-(IC1B-OUTB)") (class "Default")
      (node (ref "C34") (pin "1") (pinfunction "1_1") (pintype "passive"))
      (node (ref "IC1") (pin "7") (pinfunction "OUTB_7") (pintype "passive"))
      (node (ref "R13") (pin "2") (pinfunction "2_2") (pintype "passive"))
      (node (ref "R15") (pin "1") (pinfunction "1_1") (pintype "passive"))
    )
    (net (code "57") (name "Net-(IC2A--)") (class "Default")
      (node (ref "C43") (pin "2") (pinfunction "2_2") (pintype "passive"))
      (node (ref "IC2") (pin "2") (pinfunction "-_2") (pintype "passive"))
      (node (ref "R40") (pin "1") (pinfunction "1_1") (pintype "passive"))
      (node (ref "R41") (pin "2") (pinfunction "2_2") (pintype "passive"))
    )
    (net (code "58") (name "Net-(IC2A-OUTA)") (class "Default")
      (node (ref "C43") (pin "1") (pinfunction "1_1") (pintype "passive"))
      (node (ref "IC2") (pin "1") (pinfunction "OUTA_1") (pintype "passive"))
      (node (ref "R41") (pin "1") (pinfunction "1_1") (pintype "passive"))
      (node (ref "R60") (pin "2") (pinfunction "2_2") (pintype "passive"))
    )
    (net (code "59") (name "Net-(IC2B--)") (class "Default")
      (node (ref "C48") (pin "2") (pinfunction "2_2") (pintype "passive"))
      (node (ref "IC2") (pin "6") (pinfunction "-_6") (pintype "passive"))
      (node (ref "R52") (pin "1") (pinfunction "1_1") (pintype "passive"))
      (node (ref "R53") (pin "2") (pinfunction "2_2") (pintype "passive"))
    )
    (net (code "60") (name "Net-(IC2B-OUTB)") (class "Default")
      (node (ref "C48") (pin "1") (pinfunction "1_1") (pintype "passive"))
      (node (ref "IC2") (pin "7") (pinfunction "OUTB_7") (pintype "passive"))
      (node (ref "R53") (pin "1") (pinfunction "1_1") (pintype "passive"))
      (node (ref "R61") (pin "2") (pinfunction "2_2") (pintype "passive"))
    )
    (net (code "61") (name "Net-(IC3-LIN)") (class "Default")
      (node (ref "IC3") (pin "3") (pinfunction "LIN_3") (pintype "bidirectional"))
      (node (ref "R43") (pin "1") (pinfunction "1_1") (pintype "passive"))
    )
    (net (code "62") (name "Net-(IC3-VS)") (class "Default")
      (node (ref "C41") (pin "1") (pinfunction "1_1") (pintype "passive"))
      (node (ref "IC3") (pin "6") (pinfunction "VS_6") (pintype "bidirectional"))
    )
    (net (code "63") (name "Net-(Q1-G)") (class "Default")
      (node (ref "Q1") (pin "4") (pinfunction "G_4") (pintype "passive"))
      (node (ref "R11") (pin "1") (pinfunction "1_1") (pintype "passive"))
    )
    (net (code "64") (name "Net-(Q1-S-Pad1)") (class "Default")
      (node (ref "Q1") (pin "1") (pinfunction "S_1") (pintype "passive"))
      (node (ref "Q1") (pin "2") (pinfunction "S_2") (pintype "passive"))
      (node (ref "Q1") (pin "3") (pinfunction "S_3") (pintype "passive"))
      (node (ref "R12") (pin "2") (pinfunction "2_2") (pintype "passive"))
      (node (ref "R6") (pin "2") (pinfunction "2_2") (pintype "passive"))
    )
    (net (code "65") (name "Net-(Q2-G)") (class "Default")
      (node (ref "Q2") (pin "4") (pinfunction "G_4") (pintype "passive"))
      (node (ref "R24") (pin "1") (pinfunction "1_1") (pintype "passive"))
    )
    (net (code "66") (name "Net-(Q2-S-Pad1)") (class "Default")
      (node (ref "Q2") (pin "1") (pinfunction "S_1") (pintype "passive"))
      (node (ref "Q2") (pin "2") (pinfunction "S_2") (pintype "passive"))
      (node (ref "Q2") (pin "3") (pinfunction "S_3") (pintype "passive"))
      (node (ref "R34") (pin "2") (pinfunction "2_2") (pintype "passive"))
      (node (ref "R7") (pin "2") (pinfunction "2_2") (pintype "passive"))
    )
    (net (code "67") (name "Net-(Q3-G)") (class "Default")
      (node (ref "Q3") (pin "4") (pinfunction "G_4") (pintype "passive"))
      (node (ref "R50") (pin "1") (pinfunction "1_1") (pintype "passive"))
    )
    (net (code "68") (name "Net-(Q3-S-Pad1)") (class "Default")
      (node (ref "Q3") (pin "1") (pinfunction "S_1") (pintype "passive"))
      (node (ref "Q3") (pin "2") (pinfunction "S_2") (pintype "passive"))
      (node (ref "Q3") (pin "3") (pinfunction "S_3") (pintype "passive"))
      (node (ref "R51") (pin "2") (pinfunction "2_2") (pintype "passive"))
      (node (ref "R8") (pin "2") (pinfunction "2_2") (pintype "passive"))
    )
    (net (code "69") (name "VDD") (class "Default")
      (node (ref "L6") (pin "1") (pinfunction "1_1") (pintype "passive"))
    )
    (net (code "70") (name "unconnected-(IC3-LO-Pad5)") (class "Default")
      (node (ref "IC3") (pin "5") (pinfunction "LO_5") (pintype "bidirectional"))
    )
    (net (code "71") (name "unconnected-(U2-7B-Pad7)") (class "Default")
      (node (ref "U2") (pin "7") (pinfunction "7B_7") (pintype "passive"))
    )
    (net (code "72") (name "unconnected-(U2-7C-Pad10)") (class "Default")
      (node (ref "U2") (pin "10") (pinfunction "7C_10") (pintype "passive"))
    )
  )
)
